# Raspberry_PI.net
KiCad netlist of a schematic drawn in Altium Designer
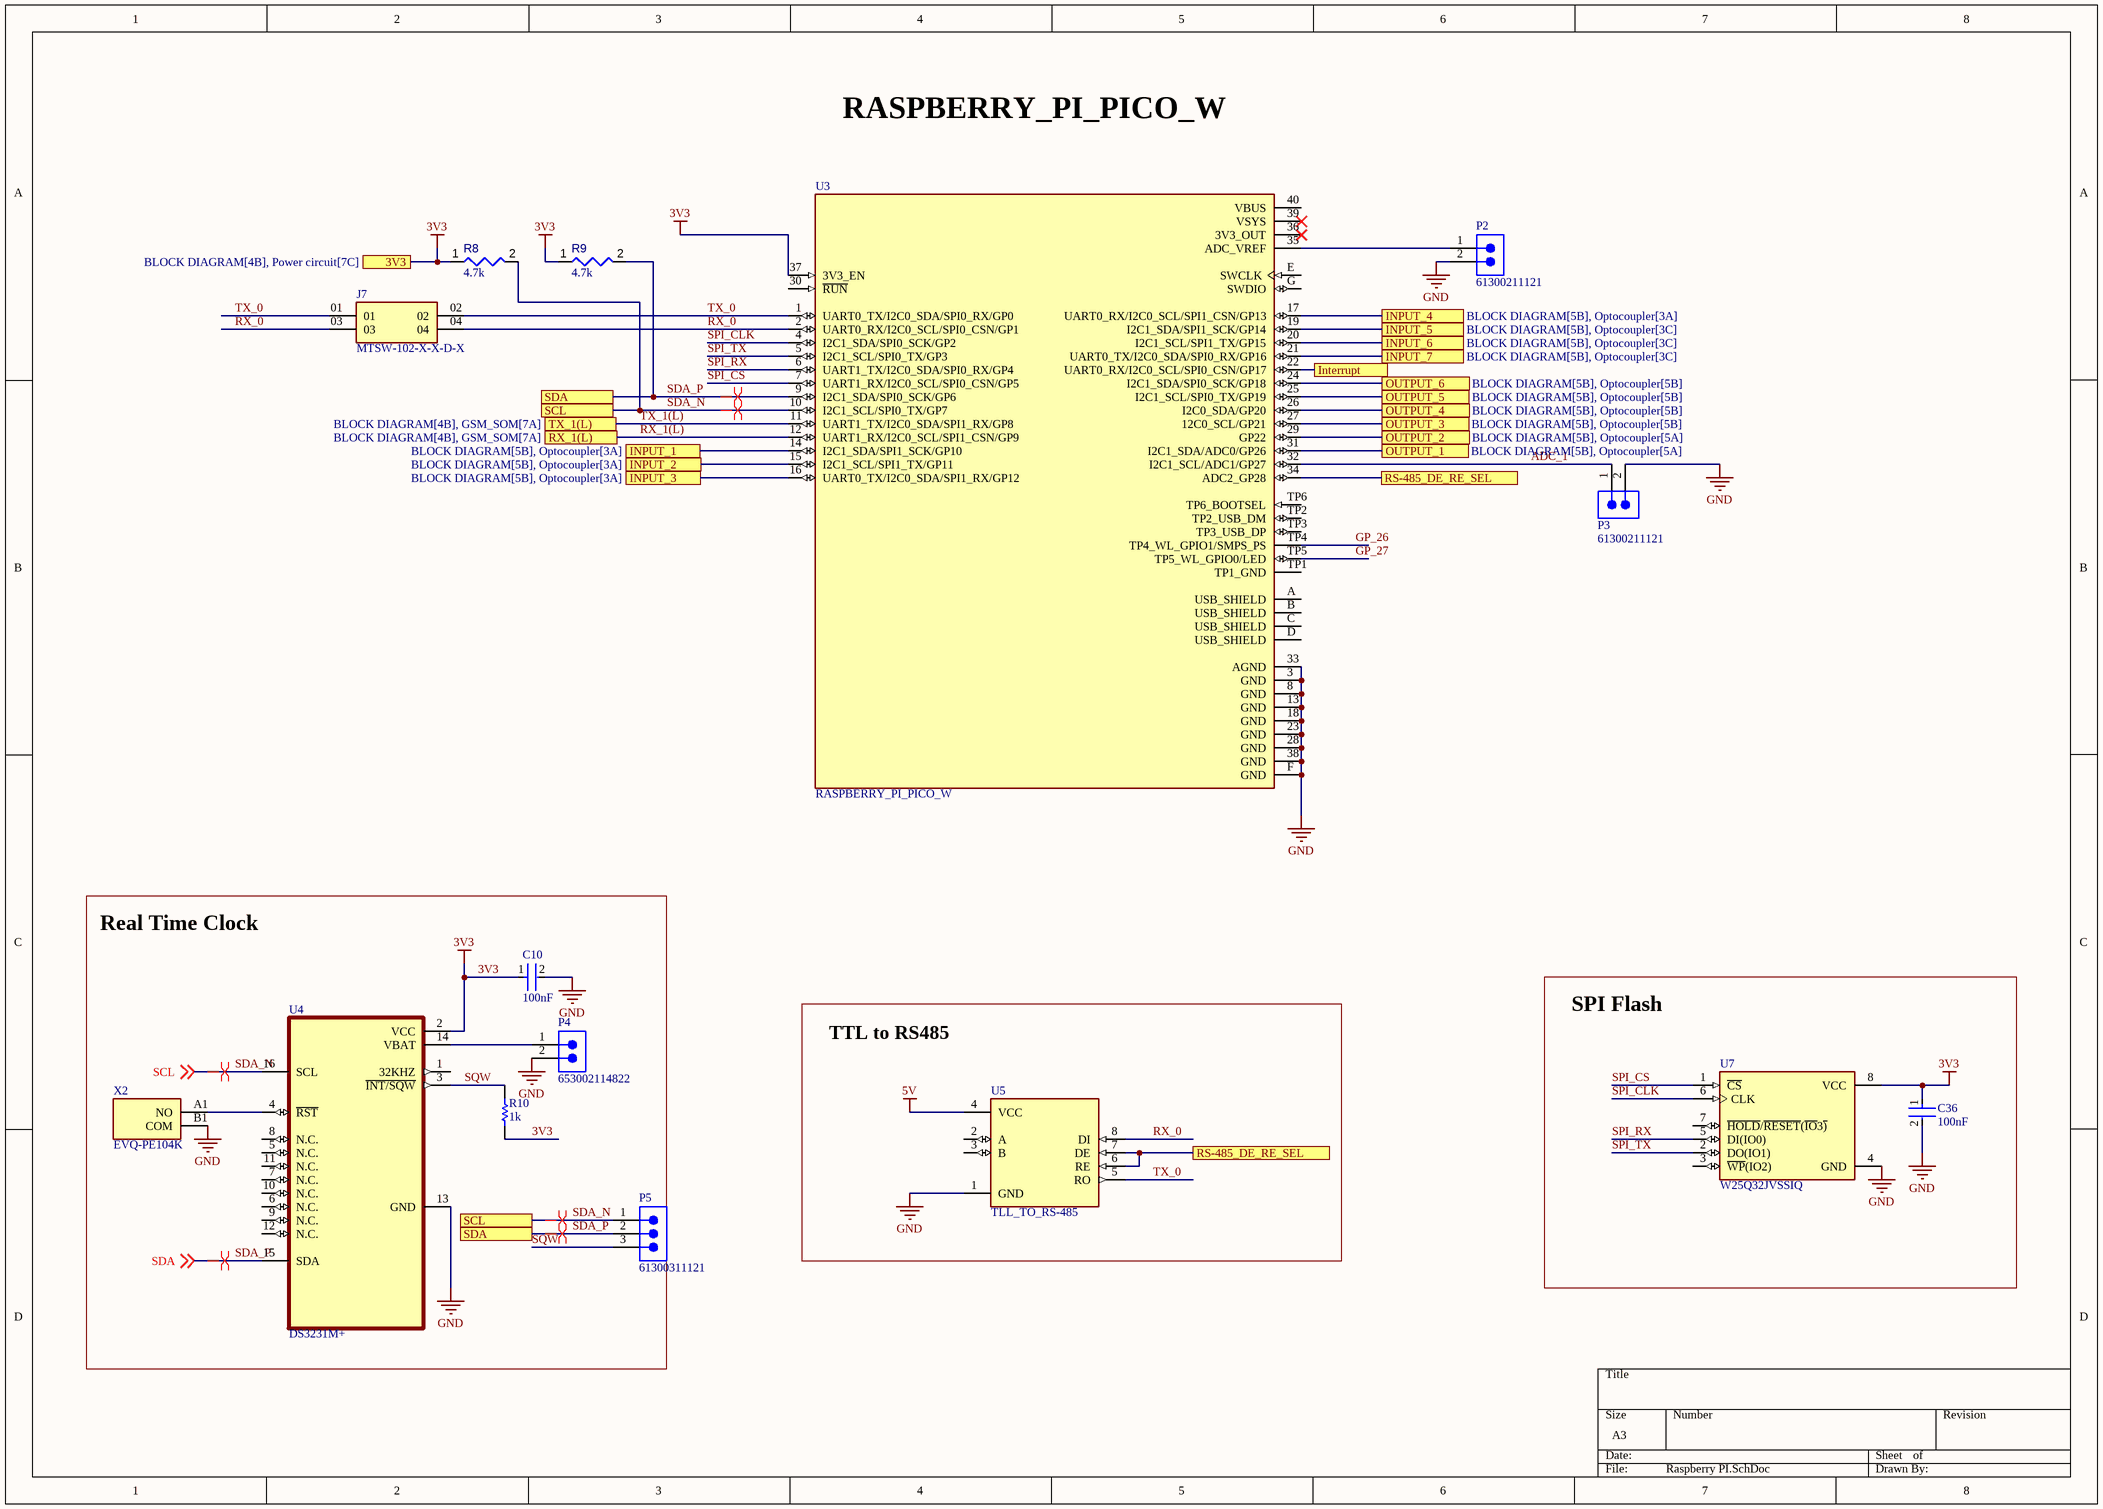
[diagram p0: Raspberry PI.SchDoc]

(export (version "E")
  (design (tool "Eeschema 10.0.6"))
  (components
    (comp (ref "C10")
      (value "100nF")
      (footprint "FP-C0402-BB-MFG")
      (description "CAP CER 0.1UF 10V X5R 0402")
      (fields (field (name "MANUFACTURER") "Kemet") (field (name "TOLERANCE") "0.1"))
      (libsource (lib "Altium Content Vault") (part "b4654b650e69147ec39a6b967a45e02"))
    )
    (comp (ref "C36")
      (value "100nF")
      (footprint "FP-C0402-BB-MFG")
      (description "CAP CER 0.1UF 10V X5R 0402")
      (fields (field (name "MANUFACTURER") "Kemet") (field (name "TOLERANCE") "0.1"))
      (libsource (lib "Altium Content Vault") (part "b4654b650e69147ec39a6b967a45e02"))
    )
    (comp (ref "J7")
      (value "MTSW-102-X-X-D-X")
      (footprint "SAMTEC_MTSW-102-X-X-D-X")
      (fields (field (name "MF") "Samtec"))
      (libsource (lib "MTSW-102-X-X-D-X") (part "MTSW-102-X-X-D-X"))
    )
    (comp (ref "P2")
      (value "61300211121")
      (footprint "61300211121")
      (libsource (lib "Altium Content Vault") (part "Header_Male_1R_02P"))
    )
    (comp (ref "P3")
      (value "61300211121")
      (footprint "61300211121")
      (libsource (lib "Altium Content Vault") (part "Header_Male_1R_02P"))
    )
    (comp (ref "P4")
      (value "653002114822")
      (footprint "653002114822")
      (libsource (lib "Altium Content Vault") (part "Header_Male_1R_02P"))
    )
    (comp (ref "P5")
      (value "61300311121")
      (footprint "61300311121")
      (libsource (lib "Altium Content Vault") (part "Header_Male_1R_03P"))
    )
    (comp (ref "R8")
      (value "4.7k")
      (footprint "RESC1005X40X25ML05T05")
      (description "Chip Resistor, 4.7 KOhm, +/- 1%, 0.1 W, -55 to 155 degC, 0402 (1005 Metric)")
      (fields (field (name "POWER") "100mW") (field (name "TOLERANCE") "1%"))
      (libsource (lib "") (part "RES-2_1"))
    )
    (comp (ref "R9")
      (value "4.7k")
      (footprint "RESC1005X40X25ML05T05")
      (description "Chip Resistor, 4.7 KOhm, +/- 1%, 0.1 W, -55 to 155 degC, 0402 (1005 Metric)")
      (fields (field (name "POWER") "100mW") (field (name "TOLERANCE") "1%"))
      (libsource (lib "") (part "RES-2_1"))
    )
    (comp (ref "R10")
      (value "1k")
      (footprint "RESC1005X40X25ML05T05")
      (description "Chip Resistor, 1 KOhm, +/- 1%, 0.1 W, -55 to 155 degC, 0402 (1005 Metric)")
      (fields (field (name "POWER") "100mW") (field (name "TOLERANCE") "1%"))
      (libsource (lib "Bannari Amman Institute of Technology") (part "RES-2"))
    )
    (comp (ref "U3")
      (value "RASPBERRY_PI_PICO_W")
      (footprint "MODULE_RASPBERRY_PI_PICO_W")
      (fields (field (name "MF") "Raspberry Pi") (field (name "MP") "RASPBERRY PI PICO W"))
      (libsource (lib "RASPBERRY_PI_PICO_W") (part "RASPBERRY_PI_PICO_W"))
    )
    (comp (ref "U4")
      (value "DS3231M+")
      (footprint "SOIC127P1032X265-16N")
      (description "Real Time Clock _RTC_ IC Clock/Calendar IÂ²C, 2-Wire Serial 8-SOIC _0.154, 3.90mm Width_")
      (fields (field (name "MP") "DS3231M") (field (name "MF") "Maxim Integrated"))
      (libsource (lib "DS3231M_") (part "DS3231M+"))
    )
    (comp (ref "U5")
      (value "TLL_TO_RS-485")
      (footprint "MODULE_MAX485_MODULE_5V_LOGIC_TLL_TO_RS-485_CONVERTER")
      (description "5V MAX485 TTL To RS485 Converter Module Board for Arduino")
      (fields
        (field (name "MP") "MAX485 Module 5V logic TLL to RS-485 converter")
        (field (name "MF") "e-Gizmo Mechatronix Central")
      )
      (libsource (lib "MAX485_MODULE_5V_LOGIC_TLL_TO_RS-485_CONVERTER") (part "MAX485_MODULE_5V_LOGIC_TLL_TO_RS-485_CONVERTER"))
    )
    (comp (ref "U7")
      (value "W25Q32JVSSIQ")
      (footprint "SOIC127P790X216-8N")
      (description "FLASH - NOR Memory IC 32Mb (4M x 8) SPI - Quad I/O 133 MHz 8-SOIC")
      (fields (field (name "MF") "Winbond"))
      (libsource (lib "W25Q32JVSSIQ") (part "W25Q32JVSSIQ"))
    )
    (comp (ref "X2")
      (value "EVQ-PE104K")
      (footprint "EVQPE104K")
      (description "Switch Tactile N.O. SPST Rectangular Button J-Bend 0.05A 12VDC 1N SMD T/R")
      (fields (field (name "MOUSER PART NUMBER") "667-EVQ-PE104K"))
      (libsource (lib "EVQ-PE104K") (part "EVQ-PE104K"))
    )
  )
  (nets
    (net (code "1") (name "/ADC_1") (class "Default")
      (node (ref "P3") (pin "1") (pinfunction "1_1") (pintype "passive"))
      (node (ref "U3") (pin "32") (pinfunction "I2C1_SCL/ADC1/GP27_32") (pintype "bidirectional"))
    )
    (net (code "2") (name "/GP_26") (class "Default")
      (node (ref "U3") (pin "TP4") (pinfunction "TP4_WL_GPIO1/SMPS_PS_TP4") (pintype "passive"))
    )
    (net (code "3") (name "/GP_27") (class "Default")
      (node (ref "U3") (pin "TP5") (pinfunction "TP5_WL_GPIO0/LED_TP5") (pintype "bidirectional"))
    )
    (net (code "4") (name "/INPUT_1") (class "Default")
      (node (ref "U3") (pin "14") (pinfunction "I2C1_SDA/SPI1_SCK/GP10_14") (pintype "bidirectional"))
    )
    (net (code "5") (name "/INPUT_2") (class "Default")
      (node (ref "U3") (pin "15") (pinfunction "I2C1_SCL/SPI1_TX/GP11_15") (pintype "bidirectional"))
    )
    (net (code "6") (name "/INPUT_3") (class "Default")
      (node (ref "U3") (pin "16") (pinfunction "UART0_TX/I2C0_SDA/SPI1_RX/GP12_16") (pintype "bidirectional"))
    )
    (net (code "7") (name "/INPUT_4") (class "Default")
      (node (ref "U3") (pin "17") (pinfunction "UART0_RX/I2C0_SCL/SPI1_CSN/GP13_17") (pintype "bidirectional"))
    )
    (net (code "8") (name "/INPUT_5") (class "Default")
      (node (ref "U3") (pin "19") (pinfunction "I2C1_SDA/SPI1_SCK/GP14_19") (pintype "bidirectional"))
    )
    (net (code "9") (name "/INPUT_6") (class "Default")
      (node (ref "U3") (pin "20") (pinfunction "I2C1_SCL/SPI1_TX/GP15_20") (pintype "bidirectional"))
    )
    (net (code "10") (name "/INPUT_7") (class "Default")
      (node (ref "U3") (pin "21") (pinfunction "UART0_TX/I2C0_SDA/SPI0_RX/GP16_21") (pintype "bidirectional"))
    )
    (net (code "11") (name "/Interrupt") (class "Default")
      (node (ref "U3") (pin "22") (pinfunction "UART0_RX/I2C0_SCL/SPI0_CSN/GP17_22") (pintype "bidirectional"))
    )
    (net (code "12") (name "/OUTPUT_1") (class "Default")
      (node (ref "U3") (pin "31") (pinfunction "I2C1_SDA/ADC0/GP26_31") (pintype "bidirectional"))
    )
    (net (code "13") (name "/OUTPUT_2") (class "Default")
      (node (ref "U3") (pin "29") (pinfunction "GP22_29") (pintype "bidirectional"))
    )
    (net (code "14") (name "/OUTPUT_3") (class "Default")
      (node (ref "U3") (pin "27") (pinfunction "12C0_SCL/GP21_27") (pintype "bidirectional"))
    )
    (net (code "15") (name "/OUTPUT_4") (class "Default")
      (node (ref "U3") (pin "26") (pinfunction "I2C0_SDA/GP20_26") (pintype "bidirectional"))
    )
    (net (code "16") (name "/OUTPUT_5") (class "Default")
      (node (ref "U3") (pin "25") (pinfunction "I2C1_SCL/SPI0_TX/GP19_25") (pintype "bidirectional"))
    )
    (net (code "17") (name "/OUTPUT_6") (class "Default")
      (node (ref "U3") (pin "24") (pinfunction "I2C1_SDA/SPI0_SCK/GP18_24") (pintype "bidirectional"))
    )
    (net (code "18") (name "/RS-485_DE_RE_SEL") (class "Default")
      (node (ref "U3") (pin "34") (pinfunction "ADC2_GP28_34") (pintype "bidirectional"))
      (node (ref "U5") (pin "6") (pinfunction "RE_6") (pintype "input"))
      (node (ref "U5") (pin "7") (pinfunction "DE_7") (pintype "input"))
    )
    (net (code "19") (name "/RX_0") (class "Default")
      (node (ref "J7") (pin "03") (pinfunction "03_03") (pintype "passive"))
      (node (ref "J7") (pin "04") (pinfunction "04_04") (pintype "passive"))
      (node (ref "U3") (pin "2") (pinfunction "UART0_RX/I2C0_SCL/SPI0_CSN/GP1_2") (pintype "bidirectional"))
      (node (ref "U5") (pin "8") (pinfunction "DI_8") (pintype "input"))
    )
    (net (code "20") (name "/RX_1(L)") (class "Default")
      (node (ref "U3") (pin "12") (pinfunction "UART1_RX/I2C0_SCL/SPI1_CSN/GP9_12") (pintype "bidirectional"))
    )
    (net (code "21") (name "/SPI_CLK") (class "Default")
      (node (ref "U3") (pin "4") (pinfunction "I2C1_SDA/SPI0_SCK/GP2_4") (pintype "bidirectional"))
      (node (ref "U7") (pin "6") (pinfunction "CLK_6") (pintype "input"))
    )
    (net (code "22") (name "/SPI_CS") (class "Default")
      (node (ref "U3") (pin "7") (pinfunction "UART1_RX/I2C0_SCL/SPI0_CSN/GP5_7") (pintype "bidirectional"))
      (node (ref "U7") (pin "1") (pinfunction "~{CS}_1") (pintype "input"))
    )
    (net (code "23") (name "/SPI_RX") (class "Default")
      (node (ref "U3") (pin "6") (pinfunction "UART1_TX/I2C0_SDA/SPI0_RX/GP4_6") (pintype "bidirectional"))
      (node (ref "U7") (pin "5") (pinfunction "DI(IO0)_5") (pintype "bidirectional"))
    )
    (net (code "24") (name "/SPI_TX") (class "Default")
      (node (ref "U3") (pin "5") (pinfunction "I2C1_SCL/SPI0_TX/GP3_5") (pintype "bidirectional"))
      (node (ref "U7") (pin "2") (pinfunction "DO(IO1)_2") (pintype "bidirectional"))
    )
    (net (code "25") (name "/SQW") (class "Default")
      (node (ref "P5") (pin "3") (pinfunction "3_3") (pintype "passive"))
      (node (ref "R10") (pin "1") (pinfunction "1_1") (pintype "passive"))
      (node (ref "U4") (pin "3") (pinfunction "~{INT/SQW}_3") (pintype "output"))
    )
    (net (code "26") (name "/TX_0") (class "Default")
      (node (ref "J7") (pin "01") (pinfunction "01_01") (pintype "passive"))
      (node (ref "J7") (pin "02") (pinfunction "02_02") (pintype "passive"))
      (node (ref "U3") (pin "1") (pinfunction "UART0_TX/I2C0_SDA/SPI0_RX/GP0_1") (pintype "bidirectional"))
      (node (ref "U5") (pin "5") (pinfunction "RO_5") (pintype "output"))
    )
    (net (code "27") (name "/TX_1(L)") (class "Default")
      (node (ref "U3") (pin "11") (pinfunction "UART1_TX/I2C0_SDA/SPI1_RX/GP8_11") (pintype "bidirectional"))
    )
    (net (code "28") (name "3V3") (class "Default")
      (node (ref "C10") (pin "1") (pinfunction "1_1") (pintype "passive"))
      (node (ref "C36") (pin "1") (pinfunction "1_1") (pintype "passive"))
      (node (ref "R10") (pin "2") (pinfunction "2_2") (pintype "passive"))
      (node (ref "R8") (pin "1") (pinfunction "1_1") (pintype "passive"))
      (node (ref "R9") (pin "1") (pinfunction "1_1") (pintype "passive"))
      (node (ref "U3") (pin "37") (pinfunction "3V3_EN_37") (pintype "input"))
      (node (ref "U4") (pin "2") (pinfunction "VCC_2") (pintype "power_in"))
      (node (ref "U7") (pin "8") (pinfunction "VCC_8") (pintype "power_in"))
    )
    (net (code "29") (name "5V") (class "Default")
      (node (ref "U5") (pin "4") (pinfunction "VCC_4") (pintype "power_in"))
    )
    (net (code "30") (name "GND") (class "Default")
      (node (ref "C10") (pin "2") (pinfunction "2_2") (pintype "passive"))
      (node (ref "C36") (pin "2") (pinfunction "2_2") (pintype "passive"))
      (node (ref "P2") (pin "2") (pinfunction "2_2") (pintype "passive"))
      (node (ref "P3") (pin "2") (pinfunction "2_2") (pintype "passive"))
      (node (ref "P4") (pin "2") (pinfunction "2_2") (pintype "passive"))
      (node (ref "U3") (pin "13") (pinfunction "GND_13") (pintype "power_in"))
      (node (ref "U3") (pin "18") (pinfunction "GND_18") (pintype "power_in"))
      (node (ref "U3") (pin "23") (pinfunction "GND_23") (pintype "power_in"))
      (node (ref "U3") (pin "28") (pinfunction "GND_28") (pintype "power_in"))
      (node (ref "U3") (pin "3") (pinfunction "GND_3") (pintype "power_in"))
      (node (ref "U3") (pin "33") (pinfunction "AGND_33") (pintype "power_in"))
      (node (ref "U3") (pin "38") (pinfunction "GND_38") (pintype "power_in"))
      (node (ref "U3") (pin "8") (pinfunction "GND_8") (pintype "power_in"))
      (node (ref "U3") (pin "F") (pinfunction "GND_F") (pintype "power_in"))
      (node (ref "U4") (pin "13") (pinfunction "GND_13") (pintype "power_in"))
      (node (ref "U5") (pin "1") (pinfunction "GND_1") (pintype "power_in"))
      (node (ref "U7") (pin "4") (pinfunction "GND_4") (pintype "power_in"))
      (node (ref "X2") (pin "B1") (pinfunction "COM_B1") (pintype "passive"))
    )
    (net (code "31") (name "Net-(U3-ADC_VREF)") (class "Default")
      (node (ref "P2") (pin "1") (pinfunction "1_1") (pintype "passive"))
      (node (ref "U3") (pin "35") (pinfunction "ADC_VREF_35") (pintype "power_in"))
    )
    (net (code "32") (name "Net-(U4-VBAT)") (class "Default")
      (node (ref "P4") (pin "1") (pinfunction "1_1") (pintype "passive"))
      (node (ref "U4") (pin "14") (pinfunction "VBAT_14") (pintype "power_in"))
    )
    (net (code "33") (name "Net-(U4-~{RST})") (class "Default")
      (node (ref "U4") (pin "4") (pinfunction "~{RST}_4") (pintype "bidirectional"))
      (node (ref "X2") (pin "A1") (pinfunction "NO_A1") (pintype "passive"))
    )
    (net (code "34") (name "SCL") (class "Default")
      (node (ref "P5") (pin "1") (pinfunction "1_1") (pintype "passive"))
      (node (ref "R8") (pin "2") (pinfunction "2_2") (pintype "passive"))
      (node (ref "U3") (pin "10") (pinfunction "I2C1_SCL/SPI0_TX/GP7_10") (pintype "bidirectional"))
      (node (ref "U4") (pin "16") (pinfunction "SCL_16") (pintype "passive"))
    )
    (net (code "35") (name "SDA") (class "Default")
      (node (ref "P5") (pin "2") (pinfunction "2_2") (pintype "passive"))
      (node (ref "R9") (pin "2") (pinfunction "2_2") (pintype "passive"))
      (node (ref "U3") (pin "9") (pinfunction "I2C1_SDA/SPI0_SCK/GP6_9") (pintype "bidirectional"))
      (node (ref "U4") (pin "15") (pinfunction "SDA_15") (pintype "passive"))
    )
    (net (code "36") (name "unconnected-(U3-3V3_OUT-Pad36)") (class "Default")
      (node (ref "U3") (pin "36") (pinfunction "3V3_OUT_36") (pintype "power_in+no_connect"))
    )
    (net (code "37") (name "unconnected-(U3-SWCLK-PadE)") (class "Default")
      (node (ref "U3") (pin "E") (pinfunction "SWCLK_E") (pintype "input"))
    )
    (net (code "38") (name "unconnected-(U3-SWDIO-PadG)") (class "Default")
      (node (ref "U3") (pin "G") (pinfunction "SWDIO_G") (pintype "bidirectional"))
    )
    (net (code "39") (name "unconnected-(U3-TP1_GND-PadTP1)") (class "Default")
      (node (ref "U3") (pin "TP1") (pinfunction "TP1_GND_TP1") (pintype "power_in"))
    )
    (net (code "40") (name "unconnected-(U3-TP2_USB_DM-PadTP2)") (class "Default")
      (node (ref "U3") (pin "TP2") (pinfunction "TP2_USB_DM_TP2") (pintype "bidirectional"))
    )
    (net (code "41") (name "unconnected-(U3-TP3_USB_DP-PadTP3)") (class "Default")
      (node (ref "U3") (pin "TP3") (pinfunction "TP3_USB_DP_TP3") (pintype "bidirectional"))
    )
    (net (code "42") (name "unconnected-(U3-TP6_BOOTSEL-PadTP6)") (class "Default")
      (node (ref "U3") (pin "TP6") (pinfunction "TP6_BOOTSEL_TP6") (pintype "input"))
    )
    (net (code "43") (name "unconnected-(U3-USB_SHIELD-PadA)") (class "Default")
      (node (ref "U3") (pin "A") (pinfunction "USB_SHIELD_A") (pintype "power_in"))
    )
    (net (code "44") (name "unconnected-(U3-USB_SHIELD-PadB)") (class "Default")
      (node (ref "U3") (pin "B") (pinfunction "USB_SHIELD_B") (pintype "power_in"))
    )
    (net (code "45") (name "unconnected-(U3-USB_SHIELD-PadC)") (class "Default")
      (node (ref "U3") (pin "C") (pinfunction "USB_SHIELD_C") (pintype "power_in"))
    )
    (net (code "46") (name "unconnected-(U3-USB_SHIELD-PadD)") (class "Default")
      (node (ref "U3") (pin "D") (pinfunction "USB_SHIELD_D") (pintype "power_in"))
    )
    (net (code "47") (name "unconnected-(U3-VBUS-Pad40)") (class "Default")
      (node (ref "U3") (pin "40") (pinfunction "VBUS_40") (pintype "power_in"))
    )
    (net (code "48") (name "unconnected-(U3-VSYS-Pad39)") (class "Default")
      (node (ref "U3") (pin "39") (pinfunction "VSYS_39") (pintype "power_in+no_connect"))
    )
    (net (code "49") (name "unconnected-(U3-~{RUN}-Pad30)") (class "Default")
      (node (ref "U3") (pin "30") (pinfunction "~{RUN}_30") (pintype "input"))
    )
    (net (code "50") (name "unconnected-(U4-32KHZ-Pad1)") (class "Default")
      (node (ref "U4") (pin "1") (pinfunction "32KHZ_1") (pintype "output"))
    )
    (net (code "51") (name "unconnected-(U4-N.C.-Pad5)") (class "Default")
      (node (ref "U4") (pin "5") (pinfunction "N.C._5") (pintype "bidirectional"))
    )
    (net (code "52") (name "unconnected-(U4-N.C.-Pad6)") (class "Default")
      (node (ref "U4") (pin "6") (pinfunction "N.C._6") (pintype "bidirectional"))
    )
    (net (code "53") (name "unconnected-(U4-N.C.-Pad7)") (class "Default")
      (node (ref "U4") (pin "7") (pinfunction "N.C._7") (pintype "bidirectional"))
    )
    (net (code "54") (name "unconnected-(U4-N.C.-Pad8)") (class "Default")
      (node (ref "U4") (pin "8") (pinfunction "N.C._8") (pintype "bidirectional"))
    )
    (net (code "55") (name "unconnected-(U4-N.C.-Pad9)") (class "Default")
      (node (ref "U4") (pin "9") (pinfunction "N.C._9") (pintype "bidirectional"))
    )
    (net (code "56") (name "unconnected-(U4-N.C.-Pad10)") (class "Default")
      (node (ref "U4") (pin "10") (pinfunction "N.C._10") (pintype "bidirectional"))
    )
    (net (code "57") (name "unconnected-(U4-N.C.-Pad11)") (class "Default")
      (node (ref "U4") (pin "11") (pinfunction "N.C._11") (pintype "bidirectional"))
    )
    (net (code "58") (name "unconnected-(U4-N.C.-Pad12)") (class "Default")
      (node (ref "U4") (pin "12") (pinfunction "N.C._12") (pintype "bidirectional"))
    )
    (net (code "59") (name "unconnected-(U5-A-Pad2)") (class "Default")
      (node (ref "U5") (pin "2") (pinfunction "A_2") (pintype "bidirectional"))
    )
    (net (code "60") (name "unconnected-(U5-B-Pad3)") (class "Default")
      (node (ref "U5") (pin "3") (pinfunction "B_3") (pintype "bidirectional"))
    )
    (net (code "61") (name "unconnected-(U7-~{HOLD}{slash}~{RESET}(~{IO}3~{)}-Pad7)") (class "Default")
      (node (ref "U7") (pin "7") (pinfunction "~{HOLD}/~{RESET}(~{IO}3~{)}_7") (pintype "bidirectional"))
    )
    (net (code "62") (name "unconnected-(U7-~{WP}(IO2)-Pad3)") (class "Default")
      (node (ref "U7") (pin "3") (pinfunction "~{WP}(IO2)_3") (pintype "bidirectional"))
    )
  )
)
